# protoboard.net
KiCad netlist of a schematic drawn in Altium Designer
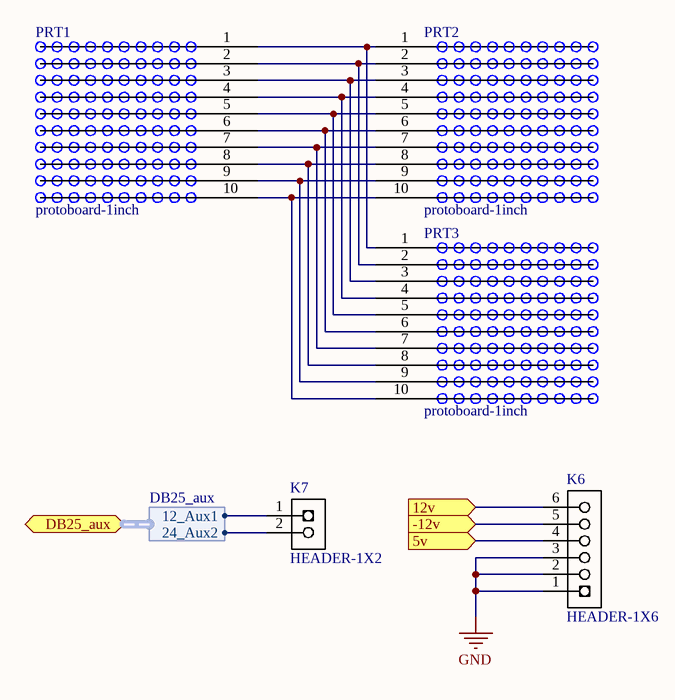
[diagram p0: protoboard.SchDoc]

(export (version "E")
  (design (tool "Eeschema 10.0.6"))
  (components
    (comp (ref "K6")
      (value "HEADER-1X6")
      (footprint "HEADER-1X6")
      (libsource (lib "TH Connectors") (part "HEADER-1X6"))
    )
    (comp (ref "K7")
      (value "HEADER-1X2")
      (footprint "HEADER-1X2")
      (libsource (lib "TH Connectors") (part "HEADER-1X2"))
    )
    (comp (ref "PRT1")
      (value "protoboard-1inch")
      (footprint "protoboard-1inch")
      (libsource (lib "custom_components") (part "protoboard-1inch"))
    )
    (comp (ref "PRT2")
      (value "protoboard-1inch")
      (footprint "protoboard-1inch")
      (libsource (lib "custom_components") (part "protoboard-1inch"))
    )
    (comp (ref "PRT3")
      (value "protoboard-1inch")
      (footprint "protoboard-1inch")
      (libsource (lib "custom_components") (part "protoboard-1inch"))
    )
  )
  (nets
    (net (code "2") (name "/-12v") (class "Default") (node (ref "K6") (pin "5") (pintype "passive")))
    (net (code "3") (name "/5v") (class "Default") (node (ref "K6") (pin "4") (pintype "passive")))
    (net (code "4") (name "/12_Aux1") (class "Default") (node (ref "K7") (pin "1") (pintype "passive")))
    (net (code "5") (name "/12v") (class "Default") (node (ref "K6") (pin "6") (pintype "passive")))
    (net (code "6") (name "/24_Aux2") (class "Default") (node (ref "K7") (pin "2") (pintype "passive")))
    (net (code "8") (name "GND") (class "Default")
      (node (ref "K6") (pin "1") (pintype "passive"))
      (node (ref "K6") (pin "2") (pintype "passive"))
      (node (ref "K6") (pin "3") (pintype "passive"))
    )
    (net (code "9") (name "Net-(PRT1-Pad1)") (class "Default")
      (node (ref "PRT1") (pin "1") (pinfunction "1_1") (pintype "passive"))
      (node (ref "PRT2") (pin "1") (pinfunction "1_1") (pintype "passive"))
      (node (ref "PRT3") (pin "1") (pinfunction "1_1") (pintype "passive"))
    )
    (net (code "10") (name "Net-(PRT1-Pad2)") (class "Default")
      (node (ref "PRT1") (pin "2") (pinfunction "2_2") (pintype "passive"))
      (node (ref "PRT2") (pin "2") (pinfunction "2_2") (pintype "passive"))
      (node (ref "PRT3") (pin "2") (pinfunction "2_2") (pintype "passive"))
    )
    (net (code "11") (name "Net-(PRT1-Pad3)") (class "Default")
      (node (ref "PRT1") (pin "3") (pinfunction "3_3") (pintype "passive"))
      (node (ref "PRT2") (pin "3") (pinfunction "3_3") (pintype "passive"))
      (node (ref "PRT3") (pin "3") (pinfunction "3_3") (pintype "passive"))
    )
    (net (code "12") (name "Net-(PRT1-Pad4)") (class "Default")
      (node (ref "PRT1") (pin "4") (pinfunction "4_4") (pintype "passive"))
      (node (ref "PRT2") (pin "4") (pinfunction "4_4") (pintype "passive"))
      (node (ref "PRT3") (pin "4") (pinfunction "4_4") (pintype "passive"))
    )
    (net (code "13") (name "Net-(PRT1-Pad5)") (class "Default")
      (node (ref "PRT1") (pin "5") (pinfunction "5_5") (pintype "passive"))
      (node (ref "PRT2") (pin "5") (pinfunction "5_5") (pintype "passive"))
      (node (ref "PRT3") (pin "5") (pinfunction "5_5") (pintype "passive"))
    )
    (net (code "14") (name "Net-(PRT1-Pad6)") (class "Default")
      (node (ref "PRT1") (pin "6") (pinfunction "6_6") (pintype "passive"))
      (node (ref "PRT2") (pin "6") (pinfunction "6_6") (pintype "passive"))
      (node (ref "PRT3") (pin "6") (pinfunction "6_6") (pintype "passive"))
    )
    (net (code "15") (name "Net-(PRT1-Pad7)") (class "Default")
      (node (ref "PRT1") (pin "7") (pinfunction "7_7") (pintype "passive"))
      (node (ref "PRT2") (pin "7") (pinfunction "7_7") (pintype "passive"))
      (node (ref "PRT3") (pin "7") (pinfunction "7_7") (pintype "passive"))
    )
    (net (code "16") (name "Net-(PRT1-Pad8)") (class "Default")
      (node (ref "PRT1") (pin "8") (pinfunction "8_8") (pintype "passive"))
      (node (ref "PRT2") (pin "8") (pinfunction "8_8") (pintype "passive"))
      (node (ref "PRT3") (pin "8") (pinfunction "8_8") (pintype "passive"))
    )
    (net (code "17") (name "Net-(PRT1-Pad9)") (class "Default")
      (node (ref "PRT1") (pin "9") (pinfunction "9_9") (pintype "passive"))
      (node (ref "PRT2") (pin "9") (pinfunction "9_9") (pintype "passive"))
      (node (ref "PRT3") (pin "9") (pinfunction "9_9") (pintype "passive"))
    )
    (net (code "18") (name "Net-(PRT1-Pad10)") (class "Default")
      (node (ref "PRT1") (pin "10") (pinfunction "10_10") (pintype "passive"))
      (node (ref "PRT2") (pin "10") (pinfunction "10_10") (pintype "passive"))
      (node (ref "PRT3") (pin "10") (pinfunction "10_10") (pintype "passive"))
    )
  )
)
